# FPGA_Decoupling.net
KiCad netlist of a schematic drawn in Altium Designer
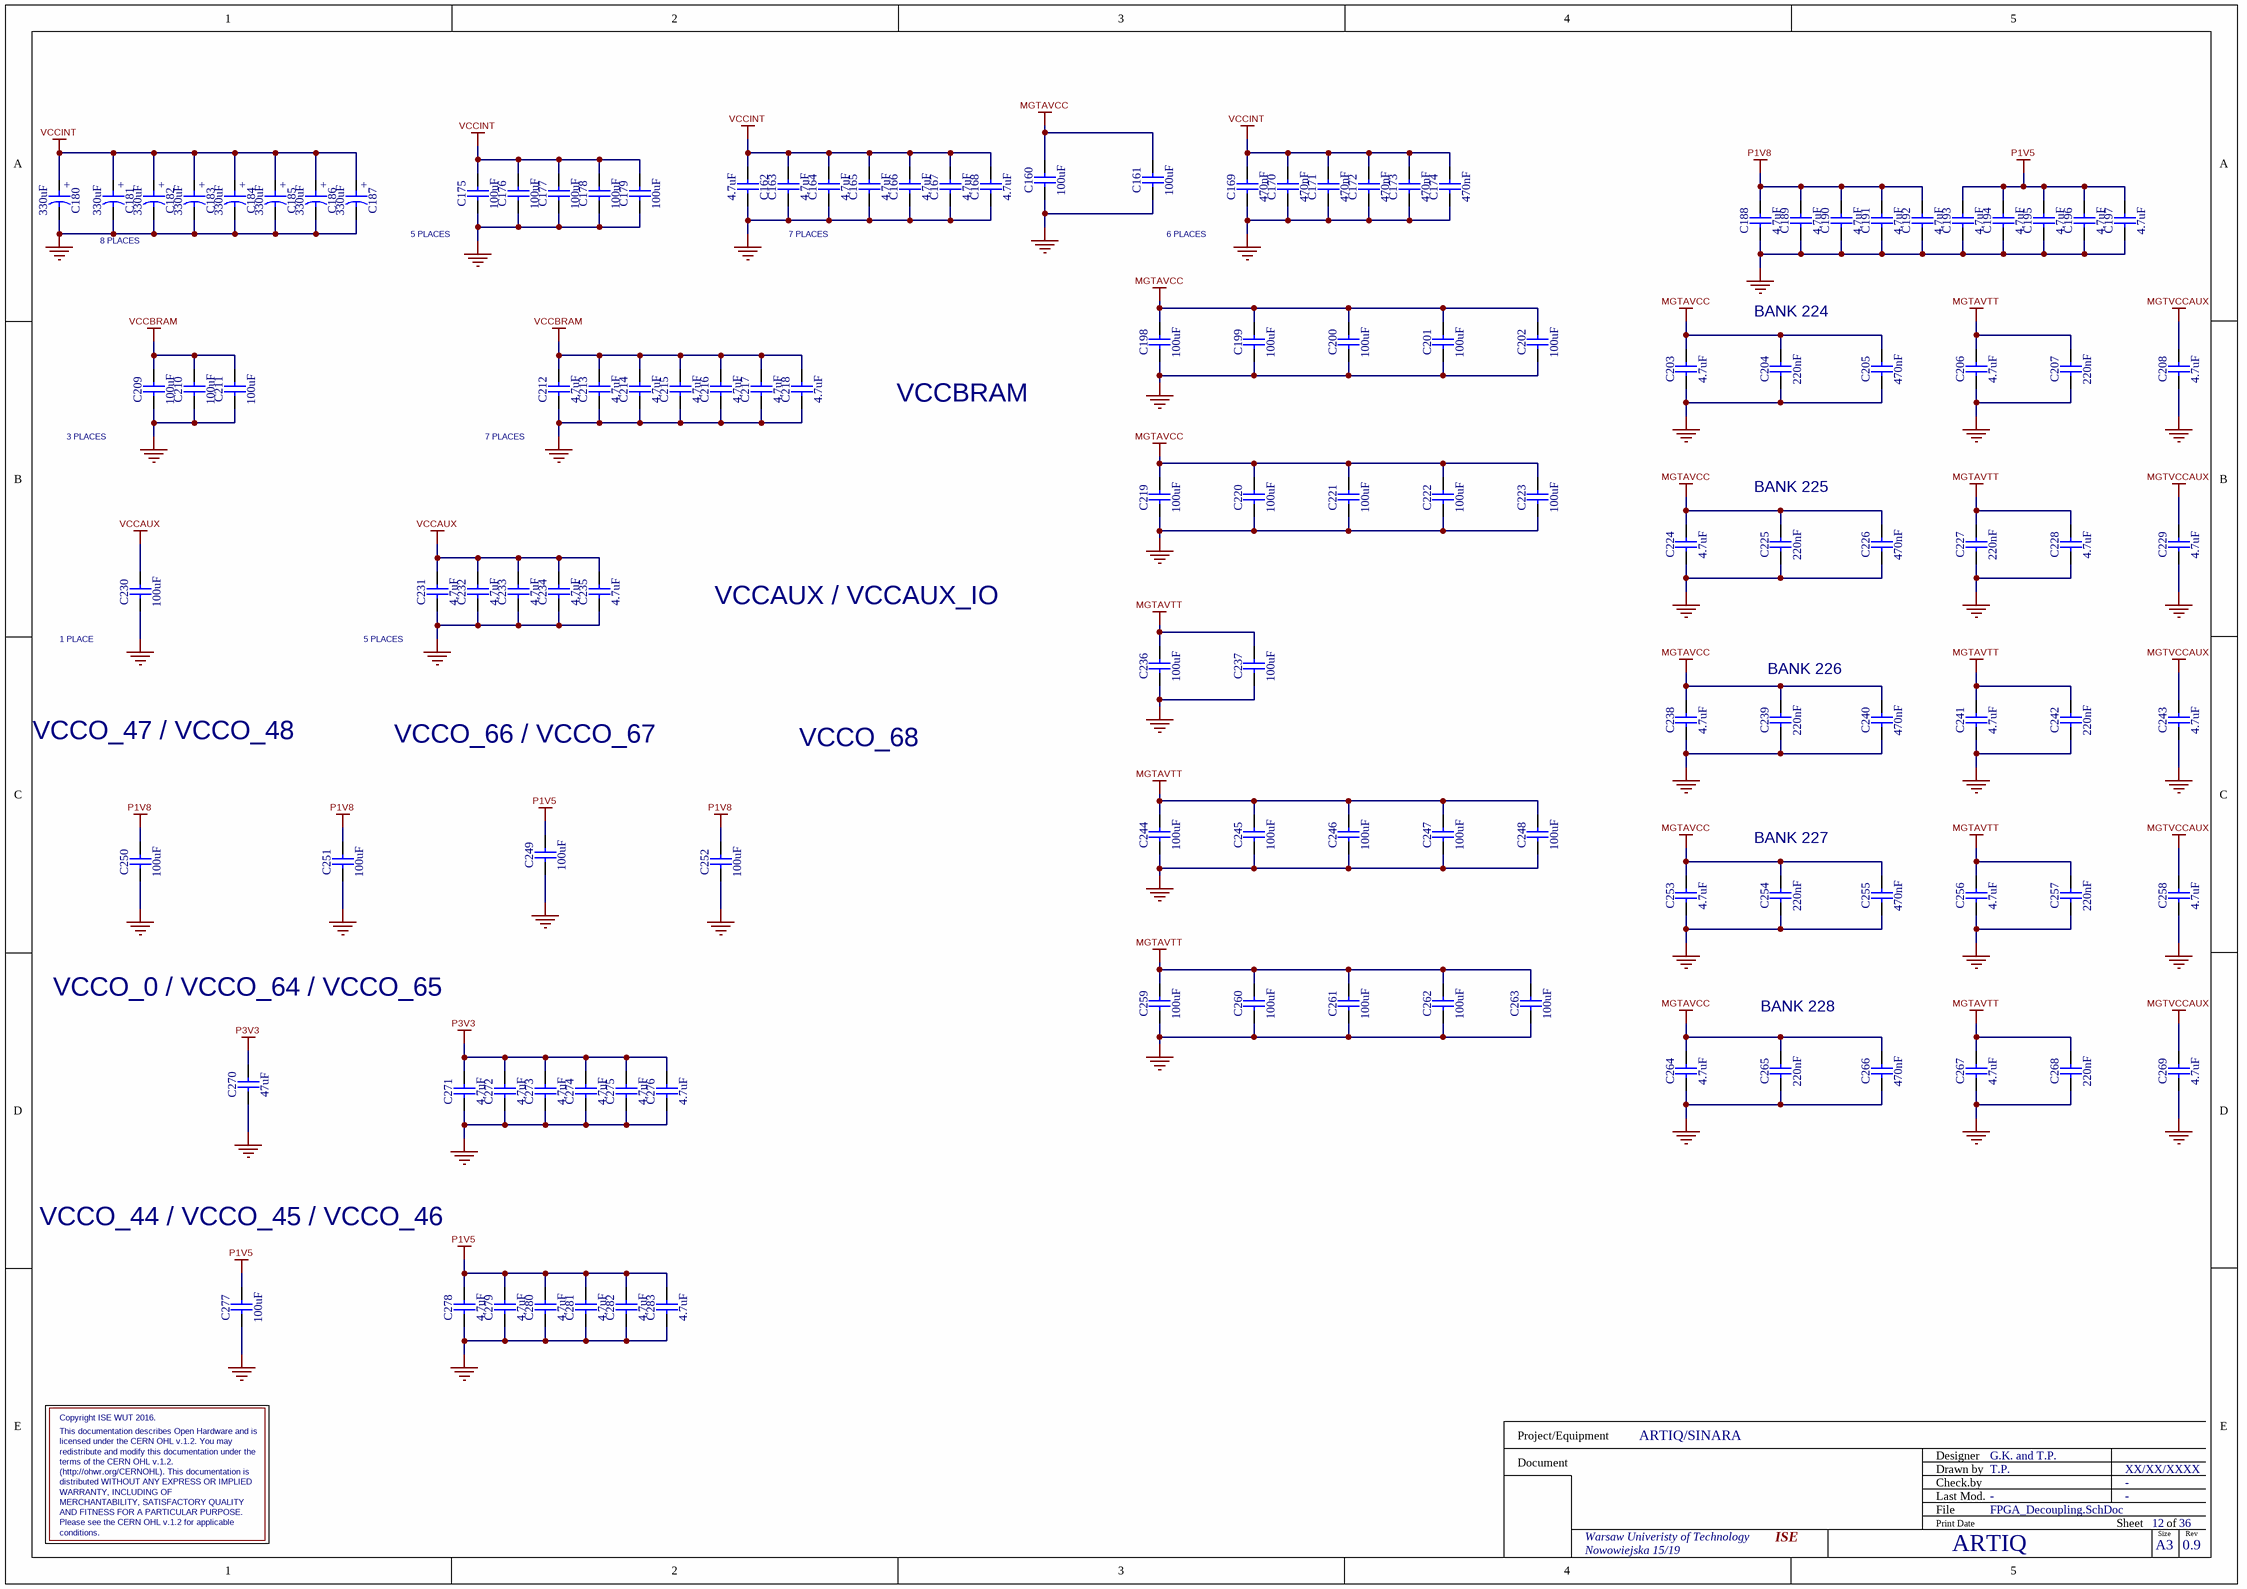
[diagram p0: FPGA_Decoupling.SchDoc]

(export (version "E")
  (design (tool "Eeschema 10.0.6"))
  (components
    (comp (ref "C160")
      (value "100uF")
      (footprint "CAPC3216X180N")
      (description "Non-polarised capacitor")
      (fields
        (field (name "MANUFACTURER PART NUMBER") "CC1206_100UF_6.3V_20%_X5R")
        (field (name "MANUFACTURER") "GENERIC")
        (field (name "AUTHOR") "CERN DEM JLC")
      )
      (libsource (lib "Capacitors") (part "Capacitor - non polarized"))
    )
    (comp (ref "C161")
      (value "100uF")
      (footprint "CAPC3216X180N")
      (description "Non-polarised capacitor")
      (fields
        (field (name "MANUFACTURER PART NUMBER") "CC1206_100UF_6.3V_20%_X5R")
        (field (name "MANUFACTURER") "GENERIC")
        (field (name "AUTHOR") "CERN DEM JLC")
      )
      (libsource (lib "Capacitors") (part "Capacitor - non polarized"))
    )
    (comp (ref "C162")
      (value "4.7uF")
      (footprint "CAPC1005X55N")
      (description "Non-polarised capacitor")
      (fields
        (field (name "MANUFACTURER PART NUMBER") "CC0402_4.7UF_6.3V_20%_X5R")
        (field (name "MANUFACTURER") "GENERIC")
        (field (name "AUTHOR") "CERN DEM JLC")
      )
      (libsource (lib "Capacitors") (part "Capacitor - non polarized"))
    )
    (comp (ref "C163")
      (value "4.7uF")
      (footprint "CAPC1005X55N")
      (description "Non-polarised capacitor")
      (fields
        (field (name "MANUFACTURER PART NUMBER") "CC0402_4.7UF_6.3V_20%_X5R")
        (field (name "MANUFACTURER") "GENERIC")
        (field (name "AUTHOR") "CERN DEM JLC")
      )
      (libsource (lib "Capacitors") (part "Capacitor - non polarized"))
    )
    (comp (ref "C164")
      (value "4.7uF")
      (footprint "CAPC1005X55N")
      (description "Non-polarised capacitor")
      (fields
        (field (name "MANUFACTURER PART NUMBER") "CC0402_4.7UF_6.3V_20%_X5R")
        (field (name "MANUFACTURER") "GENERIC")
        (field (name "AUTHOR") "CERN DEM JLC")
      )
      (libsource (lib "Capacitors") (part "Capacitor - non polarized"))
    )
    (comp (ref "C165")
      (value "4.7uF")
      (footprint "CAPC1005X55N")
      (description "Non-polarised capacitor")
      (fields
        (field (name "MANUFACTURER PART NUMBER") "CC0402_4.7UF_6.3V_20%_X5R")
        (field (name "MANUFACTURER") "GENERIC")
        (field (name "AUTHOR") "CERN DEM JLC")
      )
      (libsource (lib "Capacitors") (part "Capacitor - non polarized"))
    )
    (comp (ref "C166")
      (value "4.7uF")
      (footprint "CAPC1005X55N")
      (description "Non-polarised capacitor")
      (fields
        (field (name "MANUFACTURER PART NUMBER") "CC0402_4.7UF_6.3V_20%_X5R")
        (field (name "MANUFACTURER") "GENERIC")
        (field (name "AUTHOR") "CERN DEM JLC")
      )
      (libsource (lib "Capacitors") (part "Capacitor - non polarized"))
    )
    (comp (ref "C167")
      (value "4.7uF")
      (footprint "CAPC1005X55N")
      (description "Non-polarised capacitor")
      (fields
        (field (name "MANUFACTURER PART NUMBER") "CC0402_4.7UF_6.3V_20%_X5R")
        (field (name "MANUFACTURER") "GENERIC")
        (field (name "AUTHOR") "CERN DEM JLC")
      )
      (libsource (lib "Capacitors") (part "Capacitor - non polarized"))
    )
    (comp (ref "C168")
      (value "4.7uF")
      (footprint "CAPC1005X55N")
      (description "Non-polarised capacitor")
      (fields
        (field (name "MANUFACTURER PART NUMBER") "CC0402_4.7UF_6.3V_20%_X5R")
        (field (name "MANUFACTURER") "GENERIC")
        (field (name "AUTHOR") "CERN DEM JLC")
      )
      (libsource (lib "Capacitors") (part "Capacitor - non polarized"))
    )
    (comp (ref "C169")
      (value "470nF")
      (footprint "CAPC0603X33N")
      (description "Non-polarised capacitor")
      (fields
        (field (name "MANUFACTURER PART NUMBER") "CC0201_470NF_4V_20%_X5R")
        (field (name "MANUFACTURER") "GENERIC")
        (field (name "AUTHOR") "CERN DEM JLC")
      )
      (libsource (lib "Capacitors") (part "Capacitor - non polarized"))
    )
    (comp (ref "C170")
      (value "470nF")
      (footprint "CAPC0603X33N")
      (description "Non-polarised capacitor")
      (fields
        (field (name "MANUFACTURER PART NUMBER") "CC0201_470NF_4V_20%_X5R")
        (field (name "MANUFACTURER") "GENERIC")
        (field (name "AUTHOR") "CERN DEM JLC")
      )
      (libsource (lib "Capacitors") (part "Capacitor - non polarized"))
    )
    (comp (ref "C171")
      (value "470nF")
      (footprint "CAPC0603X33N")
      (description "Non-polarised capacitor")
      (fields
        (field (name "MANUFACTURER PART NUMBER") "CC0201_470NF_4V_20%_X5R")
        (field (name "MANUFACTURER") "GENERIC")
        (field (name "AUTHOR") "CERN DEM JLC")
      )
      (libsource (lib "Capacitors") (part "Capacitor - non polarized"))
    )
    (comp (ref "C172")
      (value "470nF")
      (footprint "CAPC0603X33N")
      (description "Non-polarised capacitor")
      (fields
        (field (name "MANUFACTURER PART NUMBER") "CC0201_470NF_4V_20%_X5R")
        (field (name "MANUFACTURER") "GENERIC")
        (field (name "AUTHOR") "CERN DEM JLC")
      )
      (libsource (lib "Capacitors") (part "Capacitor - non polarized"))
    )
    (comp (ref "C173")
      (value "470nF")
      (footprint "CAPC0603X33N")
      (description "Non-polarised capacitor")
      (fields
        (field (name "MANUFACTURER PART NUMBER") "CC0201_470NF_4V_20%_X5R")
        (field (name "MANUFACTURER") "GENERIC")
        (field (name "AUTHOR") "CERN DEM JLC")
      )
      (libsource (lib "Capacitors") (part "Capacitor - non polarized"))
    )
    (comp (ref "C174")
      (value "470nF")
      (footprint "CAPC0603X33N")
      (description "Non-polarised capacitor")
      (fields
        (field (name "MANUFACTURER PART NUMBER") "CC0201_470NF_4V_20%_X5R")
        (field (name "MANUFACTURER") "GENERIC")
        (field (name "AUTHOR") "CERN DEM JLC")
      )
      (libsource (lib "Capacitors") (part "Capacitor - non polarized"))
    )
    (comp (ref "C175")
      (value "100uF")
      (footprint "CAPC3216X180N")
      (description "Non-polarised capacitor")
      (fields
        (field (name "MANUFACTURER PART NUMBER") "CC1206_100UF_6.3V_20%_X5R")
        (field (name "MANUFACTURER") "GENERIC")
        (field (name "AUTHOR") "CERN DEM JLC")
      )
      (libsource (lib "Capacitors") (part "Capacitor - non polarized"))
    )
    (comp (ref "C176")
      (value "100uF")
      (footprint "CAPC3216X180N")
      (description "Non-polarised capacitor")
      (fields
        (field (name "MANUFACTURER PART NUMBER") "CC1206_100UF_6.3V_20%_X5R")
        (field (name "MANUFACTURER") "GENERIC")
        (field (name "AUTHOR") "CERN DEM JLC")
      )
      (libsource (lib "Capacitors") (part "Capacitor - non polarized"))
    )
    (comp (ref "C177")
      (value "100uF")
      (footprint "CAPC3216X180N")
      (description "Non-polarised capacitor")
      (fields
        (field (name "MANUFACTURER PART NUMBER") "CC1206_100UF_6.3V_20%_X5R")
        (field (name "MANUFACTURER") "GENERIC")
        (field (name "AUTHOR") "CERN DEM JLC")
      )
      (libsource (lib "Capacitors") (part "Capacitor - non polarized"))
    )
    (comp (ref "C178")
      (value "100uF")
      (footprint "CAPC3216X180N")
      (description "Non-polarised capacitor")
      (fields
        (field (name "MANUFACTURER PART NUMBER") "CC1206_100UF_6.3V_20%_X5R")
        (field (name "MANUFACTURER") "GENERIC")
        (field (name "AUTHOR") "CERN DEM JLC")
      )
      (libsource (lib "Capacitors") (part "Capacitor - non polarized"))
    )
    (comp (ref "C179")
      (value "100uF")
      (footprint "CAPC3216X180N")
      (description "Non-polarised capacitor")
      (fields
        (field (name "MANUFACTURER PART NUMBER") "CC1206_100UF_6.3V_20%_X5R")
        (field (name "MANUFACTURER") "GENERIC")
        (field (name "AUTHOR") "CERN DEM JLC")
      )
      (libsource (lib "Capacitors") (part "Capacitor - non polarized"))
    )
    (comp (ref "C180")
      (value "330uF")
      (footprint "CAPMP3528X210N")
      (description "Polarised capacitor")
      (fields
        (field (name "MANUFACTURER PART NUMBER") "T520B337M2R5ATE015")
        (field (name "MANUFACTURER") "KEMET")
        (field (name "AUTHOR") "CERN DEM JLC")
      )
      (libsource (lib "Capacitors") (part "Capacitor - polarized"))
    )
    (comp (ref "C181")
      (value "330uF")
      (footprint "CAPMP3528X210N")
      (description "Polarised capacitor")
      (fields
        (field (name "MANUFACTURER PART NUMBER") "T520B337M2R5ATE015")
        (field (name "MANUFACTURER") "KEMET")
        (field (name "AUTHOR") "CERN DEM JLC")
      )
      (libsource (lib "Capacitors") (part "Capacitor - polarized"))
    )
    (comp (ref "C182")
      (value "330uF")
      (footprint "CAPMP3528X210N")
      (description "Polarised capacitor")
      (fields
        (field (name "MANUFACTURER PART NUMBER") "T520B337M2R5ATE015")
        (field (name "MANUFACTURER") "KEMET")
        (field (name "AUTHOR") "CERN DEM JLC")
      )
      (libsource (lib "Capacitors") (part "Capacitor - polarized"))
    )
    (comp (ref "C183")
      (value "330uF")
      (footprint "CAPMP3528X210N")
      (description "Polarised capacitor")
      (fields
        (field (name "MANUFACTURER PART NUMBER") "T520B337M2R5ATE015")
        (field (name "MANUFACTURER") "KEMET")
        (field (name "AUTHOR") "CERN DEM JLC")
      )
      (libsource (lib "Capacitors") (part "Capacitor - polarized"))
    )
    (comp (ref "C184")
      (value "330uF")
      (footprint "CAPMP3528X210N")
      (description "Polarised capacitor")
      (fields
        (field (name "MANUFACTURER PART NUMBER") "T520B337M2R5ATE015")
        (field (name "MANUFACTURER") "KEMET")
        (field (name "AUTHOR") "CERN DEM JLC")
      )
      (libsource (lib "Capacitors") (part "Capacitor - polarized"))
    )
    (comp (ref "C185")
      (value "330uF")
      (footprint "CAPMP3528X210N")
      (description "Polarised capacitor")
      (fields
        (field (name "MANUFACTURER PART NUMBER") "T520B337M2R5ATE015")
        (field (name "MANUFACTURER") "KEMET")
        (field (name "AUTHOR") "CERN DEM JLC")
      )
      (libsource (lib "Capacitors") (part "Capacitor - polarized"))
    )
    (comp (ref "C186")
      (value "330uF")
      (footprint "CAPMP3528X210N")
      (description "Polarised capacitor")
      (fields
        (field (name "MANUFACTURER PART NUMBER") "T520B337M2R5ATE015")
        (field (name "MANUFACTURER") "KEMET")
        (field (name "AUTHOR") "CERN DEM JLC")
      )
      (libsource (lib "Capacitors") (part "Capacitor - polarized"))
    )
    (comp (ref "C187")
      (value "330uF")
      (footprint "CAPMP3528X210N")
      (description "Polarised capacitor")
      (fields
        (field (name "MANUFACTURER PART NUMBER") "T520B337M2R5ATE015")
        (field (name "MANUFACTURER") "KEMET")
        (field (name "AUTHOR") "CERN DEM JLC")
      )
      (libsource (lib "Capacitors") (part "Capacitor - polarized"))
    )
    (comp (ref "C188")
      (value "4.7uF")
      (footprint "CAPC1005X55N")
      (description "Non-polarised capacitor")
      (fields
        (field (name "MANUFACTURER PART NUMBER") "CC0402_4.7UF_6.3V_20%_X5R")
        (field (name "MANUFACTURER") "GENERIC")
        (field (name "AUTHOR") "CERN DEM JLC")
      )
      (libsource (lib "Capacitors") (part "Capacitor - non polarized"))
    )
    (comp (ref "C189")
      (value "4.7uF")
      (footprint "CAPC1005X55N")
      (description "Non-polarised capacitor")
      (fields
        (field (name "MANUFACTURER PART NUMBER") "CC0402_4.7UF_6.3V_20%_X5R")
        (field (name "MANUFACTURER") "GENERIC")
        (field (name "AUTHOR") "CERN DEM JLC")
      )
      (libsource (lib "Capacitors") (part "Capacitor - non polarized"))
    )
    (comp (ref "C190")
      (value "4.7uF")
      (footprint "CAPC1005X55N")
      (description "Non-polarised capacitor")
      (fields
        (field (name "MANUFACTURER PART NUMBER") "CC0402_4.7UF_6.3V_20%_X5R")
        (field (name "MANUFACTURER") "GENERIC")
        (field (name "AUTHOR") "CERN DEM JLC")
      )
      (libsource (lib "Capacitors") (part "Capacitor - non polarized"))
    )
    (comp (ref "C191")
      (value "4.7uF")
      (footprint "CAPC1005X55N")
      (description "Non-polarised capacitor")
      (fields
        (field (name "MANUFACTURER PART NUMBER") "CC0402_4.7UF_6.3V_20%_X5R")
        (field (name "MANUFACTURER") "GENERIC")
        (field (name "AUTHOR") "CERN DEM JLC")
      )
      (libsource (lib "Capacitors") (part "Capacitor - non polarized"))
    )
    (comp (ref "C192")
      (value "4.7uF")
      (footprint "CAPC1005X55N")
      (description "Non-polarised capacitor")
      (fields
        (field (name "MANUFACTURER PART NUMBER") "CC0402_4.7UF_6.3V_20%_X5R")
        (field (name "MANUFACTURER") "GENERIC")
        (field (name "AUTHOR") "CERN DEM JLC")
      )
      (libsource (lib "Capacitors") (part "Capacitor - non polarized"))
    )
    (comp (ref "C193")
      (value "4.7uF")
      (footprint "CAPC1005X55N")
      (description "Non-polarised capacitor")
      (fields
        (field (name "MANUFACTURER PART NUMBER") "CC0402_4.7UF_6.3V_20%_X5R")
        (field (name "MANUFACTURER") "GENERIC")
        (field (name "AUTHOR") "CERN DEM JLC")
      )
      (libsource (lib "Capacitors") (part "Capacitor - non polarized"))
    )
    (comp (ref "C194")
      (value "4.7uF")
      (footprint "CAPC1005X55N")
      (description "Non-polarised capacitor")
      (fields
        (field (name "MANUFACTURER PART NUMBER") "CC0402_4.7UF_6.3V_20%_X5R")
        (field (name "MANUFACTURER") "GENERIC")
        (field (name "AUTHOR") "CERN DEM JLC")
      )
      (libsource (lib "Capacitors") (part "Capacitor - non polarized"))
    )
    (comp (ref "C195")
      (value "4.7uF")
      (footprint "CAPC1005X55N")
      (description "Non-polarised capacitor")
      (fields
        (field (name "MANUFACTURER PART NUMBER") "CC0402_4.7UF_6.3V_20%_X5R")
        (field (name "MANUFACTURER") "GENERIC")
        (field (name "AUTHOR") "CERN DEM JLC")
      )
      (libsource (lib "Capacitors") (part "Capacitor - non polarized"))
    )
    (comp (ref "C196")
      (value "4.7uF")
      (footprint "CAPC1005X55N")
      (description "Non-polarised capacitor")
      (fields
        (field (name "MANUFACTURER PART NUMBER") "CC0402_4.7UF_6.3V_20%_X5R")
        (field (name "MANUFACTURER") "GENERIC")
        (field (name "AUTHOR") "CERN DEM JLC")
      )
      (libsource (lib "Capacitors") (part "Capacitor - non polarized"))
    )
    (comp (ref "C197")
      (value "4.7uF")
      (footprint "CAPC1005X55N")
      (description "Non-polarised capacitor")
      (fields
        (field (name "MANUFACTURER PART NUMBER") "CC0402_4.7UF_6.3V_20%_X5R")
        (field (name "MANUFACTURER") "GENERIC")
        (field (name "AUTHOR") "CERN DEM JLC")
      )
      (libsource (lib "Capacitors") (part "Capacitor - non polarized"))
    )
    (comp (ref "C198")
      (value "100uF")
      (footprint "CAPC3216X180N")
      (description "Non-polarised capacitor")
      (fields
        (field (name "MANUFACTURER PART NUMBER") "CC1206_100UF_6.3V_20%_X5R")
        (field (name "MANUFACTURER") "GENERIC")
        (field (name "AUTHOR") "CERN DEM JLC")
      )
      (libsource (lib "Capacitors") (part "Capacitor - non polarized"))
    )
    (comp (ref "C199")
      (value "100uF")
      (footprint "CAPC3216X180N")
      (description "Non-polarised capacitor")
      (fields
        (field (name "MANUFACTURER PART NUMBER") "CC1206_100UF_6.3V_20%_X5R")
        (field (name "MANUFACTURER") "GENERIC")
        (field (name "AUTHOR") "CERN DEM JLC")
      )
      (libsource (lib "Capacitors") (part "Capacitor - non polarized"))
    )
    (comp (ref "C200")
      (value "100uF")
      (footprint "CAPC3216X180N")
      (description "Non-polarised capacitor")
      (fields
        (field (name "MANUFACTURER PART NUMBER") "CC1206_100UF_6.3V_20%_X5R")
        (field (name "MANUFACTURER") "GENERIC")
        (field (name "AUTHOR") "CERN DEM JLC")
      )
      (libsource (lib "Capacitors") (part "Capacitor - non polarized"))
    )
    (comp (ref "C201")
      (value "100uF")
      (footprint "CAPC3216X180N")
      (description "Non-polarised capacitor")
      (fields
        (field (name "MANUFACTURER PART NUMBER") "CC1206_100UF_6.3V_20%_X5R")
        (field (name "MANUFACTURER") "GENERIC")
        (field (name "AUTHOR") "CERN DEM JLC")
      )
      (libsource (lib "Capacitors") (part "Capacitor - non polarized"))
    )
    (comp (ref "C202")
      (value "100uF")
      (footprint "CAPC3216X180N")
      (description "Non-polarised capacitor")
      (fields
        (field (name "MANUFACTURER PART NUMBER") "CC1206_100UF_6.3V_20%_X5R")
        (field (name "MANUFACTURER") "GENERIC")
        (field (name "AUTHOR") "CERN DEM JLC")
      )
      (libsource (lib "Capacitors") (part "Capacitor - non polarized"))
    )
    (comp (ref "C203")
      (value "4.7uF")
      (footprint "CAPC1005X55N")
      (description "Non-polarised capacitor")
      (fields
        (field (name "MANUFACTURER PART NUMBER") "CC0402_4.7UF_6.3V_20%_X5R")
        (field (name "MANUFACTURER") "GENERIC")
        (field (name "AUTHOR") "CERN DEM JLC")
      )
      (libsource (lib "Capacitors") (part "Capacitor - non polarized"))
    )
    (comp (ref "C204")
      (value "220nF")
      (footprint "CAPC0603X33N")
      (description "Non-polarised capacitor")
      (fields
        (field (name "MANUFACTURER PART NUMBER") "CC0201_220NF_6.3V_20%_X5R")
        (field (name "MANUFACTURER") "GENERIC")
        (field (name "AUTHOR") "CERN DEM JLC")
      )
      (libsource (lib "Capacitors") (part "Capacitor - non polarized"))
    )
    (comp (ref "C205")
      (value "470nF")
      (footprint "CAPC0603X33N")
      (description "Non-polarised capacitor")
      (fields
        (field (name "MANUFACTURER PART NUMBER") "CC0201_470NF_4V_20%_X5R")
        (field (name "MANUFACTURER") "GENERIC")
        (field (name "AUTHOR") "CERN DEM JLC")
      )
      (libsource (lib "Capacitors") (part "Capacitor - non polarized"))
    )
    (comp (ref "C206")
      (value "4.7uF")
      (footprint "CAPC1005X55N")
      (description "Non-polarised capacitor")
      (fields
        (field (name "MANUFACTURER PART NUMBER") "CC0402_4.7UF_6.3V_20%_X5R")
        (field (name "MANUFACTURER") "GENERIC")
        (field (name "AUTHOR") "CERN DEM JLC")
      )
      (libsource (lib "Capacitors") (part "Capacitor - non polarized"))
    )
    (comp (ref "C207")
      (value "220nF")
      (footprint "CAPC0603X33N")
      (description "Non-polarised capacitor")
      (fields
        (field (name "MANUFACTURER PART NUMBER") "CC0201_220NF_6.3V_20%_X5R")
        (field (name "MANUFACTURER") "GENERIC")
        (field (name "AUTHOR") "CERN DEM JLC")
      )
      (libsource (lib "Capacitors") (part "Capacitor - non polarized"))
    )
    (comp (ref "C208")
      (value "4.7uF")
      (footprint "CAPC1005X55N")
      (description "Non-polarised capacitor")
      (fields
        (field (name "MANUFACTURER PART NUMBER") "CC0402_4.7UF_6.3V_20%_X5R")
        (field (name "MANUFACTURER") "GENERIC")
        (field (name "AUTHOR") "CERN DEM JLC")
      )
      (libsource (lib "Capacitors") (part "Capacitor - non polarized"))
    )
    (comp (ref "C209")
      (value "100uF")
      (footprint "CAPC3216X180N")
      (description "Non-polarised capacitor")
      (fields
        (field (name "MANUFACTURER PART NUMBER") "CC1206_100UF_6.3V_20%_X5R")
        (field (name "MANUFACTURER") "GENERIC")
        (field (name "AUTHOR") "CERN DEM JLC")
      )
      (libsource (lib "Capacitors") (part "Capacitor - non polarized"))
    )
    (comp (ref "C210")
      (value "100uF")
      (footprint "CAPC3216X180N")
      (description "Non-polarised capacitor")
      (fields
        (field (name "MANUFACTURER PART NUMBER") "CC1206_100UF_6.3V_20%_X5R")
        (field (name "MANUFACTURER") "GENERIC")
        (field (name "AUTHOR") "CERN DEM JLC")
      )
      (libsource (lib "Capacitors") (part "Capacitor - non polarized"))
    )
    (comp (ref "C211")
      (value "100uF")
      (footprint "CAPC3216X180N")
      (description "Non-polarised capacitor")
      (fields
        (field (name "MANUFACTURER PART NUMBER") "CC1206_100UF_6.3V_20%_X5R")
        (field (name "MANUFACTURER") "GENERIC")
        (field (name "AUTHOR") "CERN DEM JLC")
      )
      (libsource (lib "Capacitors") (part "Capacitor - non polarized"))
    )
    (comp (ref "C212")
      (value "4.7uF")
      (footprint "CAPC1005X55N")
      (description "Non-polarised capacitor")
      (fields
        (field (name "MANUFACTURER PART NUMBER") "CC0402_4.7UF_6.3V_20%_X5R")
        (field (name "MANUFACTURER") "GENERIC")
        (field (name "AUTHOR") "CERN DEM JLC")
      )
      (libsource (lib "Capacitors") (part "Capacitor - non polarized"))
    )
    (comp (ref "C213")
      (value "4.7uF")
      (footprint "CAPC1005X55N")
      (description "Non-polarised capacitor")
      (fields
        (field (name "MANUFACTURER PART NUMBER") "CC0402_4.7UF_6.3V_20%_X5R")
        (field (name "MANUFACTURER") "GENERIC")
        (field (name "AUTHOR") "CERN DEM JLC")
      )
      (libsource (lib "Capacitors") (part "Capacitor - non polarized"))
    )
    (comp (ref "C214")
      (value "4.7uF")
      (footprint "CAPC1005X55N")
      (description "Non-polarised capacitor")
      (fields
        (field (name "MANUFACTURER PART NUMBER") "CC0402_4.7UF_6.3V_20%_X5R")
        (field (name "MANUFACTURER") "GENERIC")
        (field (name "AUTHOR") "CERN DEM JLC")
      )
      (libsource (lib "Capacitors") (part "Capacitor - non polarized"))
    )
    (comp (ref "C215")
      (value "4.7uF")
      (footprint "CAPC1005X55N")
      (description "Non-polarised capacitor")
      (fields
        (field (name "MANUFACTURER PART NUMBER") "CC0402_4.7UF_6.3V_20%_X5R")
        (field (name "MANUFACTURER") "GENERIC")
        (field (name "AUTHOR") "CERN DEM JLC")
      )
      (libsource (lib "Capacitors") (part "Capacitor - non polarized"))
    )
    (comp (ref "C216")
      (value "4.7uF")
      (footprint "CAPC1005X55N")
      (description "Non-polarised capacitor")
      (fields
        (field (name "MANUFACTURER PART NUMBER") "CC0402_4.7UF_6.3V_20%_X5R")
        (field (name "MANUFACTURER") "GENERIC")
        (field (name "AUTHOR") "CERN DEM JLC")
      )
      (libsource (lib "Capacitors") (part "Capacitor - non polarized"))
    )
    (comp (ref "C217")
      (value "4.7uF")
      (footprint "CAPC1005X55N")
      (description "Non-polarised capacitor")
      (fields
        (field (name "MANUFACTURER PART NUMBER") "CC0402_4.7UF_6.3V_20%_X5R")
        (field (name "MANUFACTURER") "GENERIC")
        (field (name "AUTHOR") "CERN DEM JLC")
      )
      (libsource (lib "Capacitors") (part "Capacitor - non polarized"))
    )
    (comp (ref "C218")
      (value "4.7uF")
      (footprint "CAPC1005X55N")
      (description "Non-polarised capacitor")
      (fields
        (field (name "MANUFACTURER PART NUMBER") "CC0402_4.7UF_6.3V_20%_X5R")
        (field (name "MANUFACTURER") "GENERIC")
        (field (name "AUTHOR") "CERN DEM JLC")
      )
      (libsource (lib "Capacitors") (part "Capacitor - non polarized"))
    )
    (comp (ref "C219")
      (value "100uF")
      (footprint "CAPC3216X180N")
      (description "Non-polarised capacitor")
      (fields
        (field (name "MANUFACTURER PART NUMBER") "CC1206_100UF_6.3V_20%_X5R")
        (field (name "MANUFACTURER") "GENERIC")
        (field (name "AUTHOR") "CERN DEM JLC")
      )
      (libsource (lib "Capacitors") (part "Capacitor - non polarized"))
    )
    (comp (ref "C220")
      (value "100uF")
      (footprint "CAPC3216X180N")
      (description "Non-polarised capacitor")
      (fields
        (field (name "MANUFACTURER PART NUMBER") "CC1206_100UF_6.3V_20%_X5R")
        (field (name "MANUFACTURER") "GENERIC")
        (field (name "AUTHOR") "CERN DEM JLC")
      )
      (libsource (lib "Capacitors") (part "Capacitor - non polarized"))
    )
    (comp (ref "C221")
      (value "100uF")
      (footprint "CAPC3216X180N")
      (description "Non-polarised capacitor")
      (fields
        (field (name "MANUFACTURER PART NUMBER") "CC1206_100UF_6.3V_20%_X5R")
        (field (name "MANUFACTURER") "GENERIC")
        (field (name "AUTHOR") "CERN DEM JLC")
      )
      (libsource (lib "Capacitors") (part "Capacitor - non polarized"))
    )
    (comp (ref "C222")
      (value "100uF")
      (footprint "CAPC3216X180N")
      (description "Non-polarised capacitor")
      (fields
        (field (name "MANUFACTURER PART NUMBER") "CC1206_100UF_6.3V_20%_X5R")
        (field (name "MANUFACTURER") "GENERIC")
        (field (name "AUTHOR") "CERN DEM JLC")
      )
      (libsource (lib "Capacitors") (part "Capacitor - non polarized"))
    )
    (comp (ref "C223")
      (value "100uF")
      (footprint "CAPC3216X180N")
      (description "Non-polarised capacitor")
      (fields
        (field (name "MANUFACTURER PART NUMBER") "CC1206_100UF_6.3V_20%_X5R")
        (field (name "MANUFACTURER") "GENERIC")
        (field (name "AUTHOR") "CERN DEM JLC")
      )
      (libsource (lib "Capacitors") (part "Capacitor - non polarized"))
    )
    (comp (ref "C224")
      (value "4.7uF")
      (footprint "CAPC1005X55N")
      (description "Non-polarised capacitor")
      (fields
        (field (name "MANUFACTURER PART NUMBER") "CC0402_4.7UF_6.3V_20%_X5R")
        (field (name "MANUFACTURER") "GENERIC")
        (field (name "AUTHOR") "CERN DEM JLC")
      )
      (libsource (lib "Capacitors") (part "Capacitor - non polarized"))
    )
    (comp (ref "C225")
      (value "220nF")
      (footprint "CAPC0603X33N")
      (description "Non-polarised capacitor")
      (fields
        (field (name "MANUFACTURER PART NUMBER") "CC0201_220NF_6.3V_20%_X5R")
        (field (name "MANUFACTURER") "GENERIC")
        (field (name "AUTHOR") "CERN DEM JLC")
      )
      (libsource (lib "Capacitors") (part "Capacitor - non polarized"))
    )
    (comp (ref "C226")
      (value "470nF")
      (footprint "CAPC0603X33N")
      (description "Non-polarised capacitor")
      (fields
        (field (name "MANUFACTURER PART NUMBER") "CC0201_470NF_4V_20%_X5R")
        (field (name "MANUFACTURER") "GENERIC")
        (field (name "AUTHOR") "CERN DEM JLC")
      )
      (libsource (lib "Capacitors") (part "Capacitor - non polarized"))
    )
    (comp (ref "C227")
      (value "220nF")
      (footprint "CAPC0603X33N")
      (description "Non-polarised capacitor")
      (fields
        (field (name "MANUFACTURER PART NUMBER") "CC0201_220NF_6.3V_20%_X5R")
        (field (name "MANUFACTURER") "GENERIC")
        (field (name "AUTHOR") "CERN DEM JLC")
      )
      (libsource (lib "Capacitors") (part "Capacitor - non polarized"))
    )
    (comp (ref "C228")
      (value "4.7uF")
      (footprint "CAPC1005X55N")
      (description "Non-polarised capacitor")
      (fields
        (field (name "MANUFACTURER PART NUMBER") "CC0402_4.7UF_6.3V_20%_X5R")
        (field (name "MANUFACTURER") "GENERIC")
        (field (name "AUTHOR") "CERN DEM JLC")
      )
      (libsource (lib "Capacitors") (part "Capacitor - non polarized"))
    )
    (comp (ref "C229")
      (value "4.7uF")
      (footprint "CAPC1005X55N")
      (description "Non-polarised capacitor")
      (fields
        (field (name "MANUFACTURER PART NUMBER") "CC0402_4.7UF_6.3V_20%_X5R")
        (field (name "MANUFACTURER") "GENERIC")
        (field (name "AUTHOR") "CERN DEM JLC")
      )
      (libsource (lib "Capacitors") (part "Capacitor - non polarized"))
    )
    (comp (ref "C230")
      (value "100uF")
      (footprint "CAPC3216X180N")
      (description "Non-polarised capacitor")
      (fields
        (field (name "MANUFACTURER PART NUMBER") "CC1206_100UF_6.3V_20%_X5R")
        (field (name "MANUFACTURER") "GENERIC")
        (field (name "AUTHOR") "CERN DEM JLC")
      )
      (libsource (lib "Capacitors") (part "Capacitor - non polarized"))
    )
    (comp (ref "C231")
      (value "4.7uF")
      (footprint "CAPC1005X55N")
      (description "Non-polarised capacitor")
      (fields
        (field (name "MANUFACTURER PART NUMBER") "CC0402_4.7UF_6.3V_20%_X5R")
        (field (name "MANUFACTURER") "GENERIC")
        (field (name "AUTHOR") "CERN DEM JLC")
      )
      (libsource (lib "Capacitors") (part "Capacitor - non polarized"))
    )
    (comp (ref "C232")
      (value "4.7uF")
      (footprint "CAPC1005X55N")
      (description "Non-polarised capacitor")
      (fields
        (field (name "MANUFACTURER PART NUMBER") "CC0402_4.7UF_6.3V_20%_X5R")
        (field (name "MANUFACTURER") "GENERIC")
        (field (name "AUTHOR") "CERN DEM JLC")
      )
      (libsource (lib "Capacitors") (part "Capacitor - non polarized"))
    )
    (comp (ref "C233")
      (value "4.7uF")
      (footprint "CAPC1005X55N")
      (description "Non-polarised capacitor")
      (fields
        (field (name "MANUFACTURER PART NUMBER") "CC0402_4.7UF_6.3V_20%_X5R")
        (field (name "MANUFACTURER") "GENERIC")
        (field (name "AUTHOR") "CERN DEM JLC")
      )
      (libsource (lib "Capacitors") (part "Capacitor - non polarized"))
    )
    (comp (ref "C234")
      (value "4.7uF")
      (footprint "CAPC1005X55N")
      (description "Non-polarised capacitor")
      (fields
        (field (name "MANUFACTURER PART NUMBER") "CC0402_4.7UF_6.3V_20%_X5R")
        (field (name "MANUFACTURER") "GENERIC")
        (field (name "AUTHOR") "CERN DEM JLC")
      )
      (libsource (lib "Capacitors") (part "Capacitor - non polarized"))
    )
    (comp (ref "C235")
      (value "4.7uF")
      (footprint "CAPC1005X55N")
      (description "Non-polarised capacitor")
      (fields
        (field (name "MANUFACTURER PART NUMBER") "CC0402_4.7UF_6.3V_20%_X5R")
        (field (name "MANUFACTURER") "GENERIC")
        (field (name "AUTHOR") "CERN DEM JLC")
      )
      (libsource (lib "Capacitors") (part "Capacitor - non polarized"))
    )
    (comp (ref "C236")
      (value "100uF")
      (footprint "CAPC3216X180N")
      (description "Non-polarised capacitor")
      (fields
        (field (name "MANUFACTURER PART NUMBER") "CC1206_100UF_6.3V_20%_X5R")
        (field (name "MANUFACTURER") "GENERIC")
        (field (name "AUTHOR") "CERN DEM JLC")
      )
      (libsource (lib "Capacitors") (part "Capacitor - non polarized"))
    )
    (comp (ref "C237")
      (value "100uF")
      (footprint "CAPC3216X180N")
      (description "Non-polarised capacitor")
      (fields
        (field (name "MANUFACTURER PART NUMBER") "CC1206_100UF_6.3V_20%_X5R")
        (field (name "MANUFACTURER") "GENERIC")
        (field (name "AUTHOR") "CERN DEM JLC")
      )
      (libsource (lib "Capacitors") (part "Capacitor - non polarized"))
    )
    (comp (ref "C238")
      (value "4.7uF")
      (footprint "CAPC1005X55N")
      (description "Non-polarised capacitor")
      (fields
        (field (name "MANUFACTURER PART NUMBER") "CC0402_4.7UF_6.3V_20%_X5R")
        (field (name "MANUFACTURER") "GENERIC")
        (field (name "AUTHOR") "CERN DEM JLC")
      )
      (libsource (lib "Capacitors") (part "Capacitor - non polarized"))
    )
    (comp (ref "C239")
      (value "220nF")
      (footprint "CAPC0603X33N")
      (description "Non-polarised capacitor")
      (fields
        (field (name "MANUFACTURER PART NUMBER") "CC0201_220NF_6.3V_20%_X5R")
        (field (name "MANUFACTURER") "GENERIC")
        (field (name "AUTHOR") "CERN DEM JLC")
      )
      (libsource (lib "Capacitors") (part "Capacitor - non polarized"))
    )
    (comp (ref "C240")
      (value "470nF")
      (footprint "CAPC0603X33N")
      (description "Non-polarised capacitor")
      (fields
        (field (name "MANUFACTURER PART NUMBER") "CC0201_470NF_4V_20%_X5R")
        (field (name "MANUFACTURER") "GENERIC")
        (field (name "AUTHOR") "CERN DEM JLC")
      )
      (libsource (lib "Capacitors") (part "Capacitor - non polarized"))
    )
    (comp (ref "C241")
      (value "4.7uF")
      (footprint "CAPC1005X55N")
      (description "Non-polarised capacitor")
      (fields
        (field (name "MANUFACTURER PART NUMBER") "CC0402_4.7UF_6.3V_20%_X5R")
        (field (name "MANUFACTURER") "GENERIC")
        (field (name "AUTHOR") "CERN DEM JLC")
      )
      (libsource (lib "Capacitors") (part "Capacitor - non polarized"))
    )
    (comp (ref "C242")
      (value "220nF")
      (footprint "CAPC0603X33N")
      (description "Non-polarised capacitor")
      (fields
        (field (name "MANUFACTURER PART NUMBER") "CC0201_220NF_6.3V_20%_X5R")
        (field (name "MANUFACTURER") "GENERIC")
        (field (name "AUTHOR") "CERN DEM JLC")
      )
      (libsource (lib "Capacitors") (part "Capacitor - non polarized"))
    )
    (comp (ref "C243")
      (value "4.7uF")
      (footprint "CAPC1005X55N")
      (description "Non-polarised capacitor")
      (fields
        (field (name "MANUFACTURER PART NUMBER") "CC0402_4.7UF_6.3V_20%_X5R")
        (field (name "MANUFACTURER") "GENERIC")
        (field (name "AUTHOR") "CERN DEM JLC")
      )
      (libsource (lib "Capacitors") (part "Capacitor - non polarized"))
    )
    (comp (ref "C244")
      (value "100uF")
      (footprint "CAPC3216X180N")
      (description "Non-polarised capacitor")
      (fields
        (field (name "MANUFACTURER PART NUMBER") "CC1206_100UF_6.3V_20%_X5R")
        (field (name "MANUFACTURER") "GENERIC")
        (field (name "AUTHOR") "CERN DEM JLC")
      )
      (libsource (lib "Capacitors") (part "Capacitor - non polarized"))
    )
    (comp (ref "C245")
      (value "100uF")
      (footprint "CAPC3216X180N")
      (description "Non-polarised capacitor")
      (fields
        (field (name "MANUFACTURER PART NUMBER") "CC1206_100UF_6.3V_20%_X5R")
        (field (name "MANUFACTURER") "GENERIC")
        (field (name "AUTHOR") "CERN DEM JLC")
      )
      (libsource (lib "Capacitors") (part "Capacitor - non polarized"))
    )
    (comp (ref "C246")
      (value "100uF")
      (footprint "CAPC3216X180N")
      (description "Non-polarised capacitor")
      (fields
        (field (name "MANUFACTURER PART NUMBER") "CC1206_100UF_6.3V_20%_X5R")
        (field (name "MANUFACTURER") "GENERIC")
        (field (name "AUTHOR") "CERN DEM JLC")
      )
      (libsource (lib "Capacitors") (part "Capacitor - non polarized"))
    )
    (comp (ref "C247")
      (value "100uF")
      (footprint "CAPC3216X180N")
      (description "Non-polarised capacitor")
      (fields
        (field (name "MANUFACTURER PART NUMBER") "CC1206_100UF_6.3V_20%_X5R")
        (field (name "MANUFACTURER") "GENERIC")
        (field (name "AUTHOR") "CERN DEM JLC")
      )
      (libsource (lib "Capacitors") (part "Capacitor - non polarized"))
    )
    (comp (ref "C248")
      (value "100uF")
      (footprint "CAPC3216X180N")
      (description "Non-polarised capacitor")
      (fields
        (field (name "MANUFACTURER PART NUMBER") "CC1206_100UF_6.3V_20%_X5R")
        (field (name "MANUFACTURER") "GENERIC")
        (field (name "AUTHOR") "CERN DEM JLC")
      )
      (libsource (lib "Capacitors") (part "Capacitor - non polarized"))
    )
    (comp (ref "C249")
      (value "100uF")
      (footprint "CAPC3216X180N")
      (description "Non-polarised capacitor")
      (fields
        (field (name "MANUFACTURER PART NUMBER") "CC1206_100UF_6.3V_20%_X5R")
        (field (name "MANUFACTURER") "GENERIC")
        (field (name "AUTHOR") "CERN DEM JLC")
      )
      (libsource (lib "Capacitors") (part "Capacitor - non polarized"))
    )
    (comp (ref "C250")
      (value "100uF")
      (footprint "CAPC3216X180N")
      (description "Non-polarised capacitor")
      (fields
        (field (name "MANUFACTURER PART NUMBER") "CC1206_100UF_6.3V_20%_X5R")
        (field (name "MANUFACTURER") "GENERIC")
        (field (name "AUTHOR") "CERN DEM JLC")
      )
      (libsource (lib "Capacitors") (part "Capacitor - non polarized"))
    )
    (comp (ref "C251")
      (value "100uF")
      (footprint "CAPC3216X180N")
      (description "Non-polarised capacitor")
      (fields
        (field (name "MANUFACTURER PART NUMBER") "CC1206_100UF_6.3V_20%_X5R")
        (field (name "MANUFACTURER") "GENERIC")
        (field (name "AUTHOR") "CERN DEM JLC")
      )
      (libsource (lib "Capacitors") (part "Capacitor - non polarized"))
    )
    (comp (ref "C252")
      (value "100uF")
      (footprint "CAPC3216X180N")
      (description "Non-polarised capacitor")
      (fields
        (field (name "MANUFACTURER PART NUMBER") "CC1206_100UF_6.3V_20%_X5R")
        (field (name "MANUFACTURER") "GENERIC")
        (field (name "AUTHOR") "CERN DEM JLC")
      )
      (libsource (lib "Capacitors") (part "Capacitor - non polarized"))
    )
    (comp (ref "C253")
      (value "4.7uF")
      (footprint "CAPC1005X55N")
      (description "Non-polarised capacitor")
      (fields
        (field (name "MANUFACTURER PART NUMBER") "CC0402_4.7UF_6.3V_20%_X5R")
        (field (name "MANUFACTURER") "GENERIC")
        (field (name "AUTHOR") "CERN DEM JLC")
      )
      (libsource (lib "Capacitors") (part "Capacitor - non polarized"))
    )
    (comp (ref "C254")
      (value "220nF")
      (footprint "CAPC0603X33N")
      (description "Non-polarised capacitor")
      (fields
        (field (name "MANUFACTURER PART NUMBER") "CC0201_220NF_6.3V_20%_X5R")
        (field (name "MANUFACTURER") "GENERIC")
        (field (name "AUTHOR") "CERN DEM JLC")
      )
      (libsource (lib "Capacitors") (part "Capacitor - non polarized"))
    )
    (comp (ref "C255")
      (value "470nF")
      (footprint "CAPC0603X33N")
      (description "Non-polarised capacitor")
      (fields
        (field (name "MANUFACTURER PART NUMBER") "CC0201_470NF_4V_20%_X5R")
        (field (name "MANUFACTURER") "GENERIC")
        (field (name "AUTHOR") "CERN DEM JLC")
      )
      (libsource (lib "Capacitors") (part "Capacitor - non polarized"))
    )
    (comp (ref "C256")
      (value "4.7uF")
      (footprint "CAPC1005X55N")
      (description "Non-polarised capacitor")
      (fields
        (field (name "MANUFACTURER PART NUMBER") "CC0402_4.7UF_6.3V_20%_X5R")
        (field (name "MANUFACTURER") "GENERIC")
        (field (name "AUTHOR") "CERN DEM JLC")
      )
      (libsource (lib "Capacitors") (part "Capacitor - non polarized"))
    )
    (comp (ref "C257")
      (value "220nF")
      (footprint "CAPC0603X33N")
      (description "Non-polarised capacitor")
      (fields
        (field (name "MANUFACTURER PART NUMBER") "CC0201_220NF_6.3V_20%_X5R")
        (field (name "MANUFACTURER") "GENERIC")
        (field (name "AUTHOR") "CERN DEM JLC")
      )
      (libsource (lib "Capacitors") (part "Capacitor - non polarized"))
    )
    (comp (ref "C258")
      (value "4.7uF")
      (footprint "CAPC1005X55N")
      (description "Non-polarised capacitor")
      (fields
        (field (name "MANUFACTURER PART NUMBER") "CC0402_4.7UF_6.3V_20%_X5R")
        (field (name "MANUFACTURER") "GENERIC")
        (field (name "AUTHOR") "CERN DEM JLC")
      )
      (libsource (lib "Capacitors") (part "Capacitor - non polarized"))
    )
    (comp (ref "C259")
      (value "100uF")
      (footprint "CAPC3216X180N")
      (description "Non-polarised capacitor")
      (fields
        (field (name "MANUFACTURER PART NUMBER") "CC1206_100UF_6.3V_20%_X5R")
        (field (name "MANUFACTURER") "GENERIC")
        (field (name "AUTHOR") "CERN DEM JLC")
      )
      (libsource (lib "Capacitors") (part "Capacitor - non polarized"))
    )
    (comp (ref "C260")
      (value "100uF")
      (footprint "CAPC3216X180N")
      (description "Non-polarised capacitor")
      (fields
        (field (name "MANUFACTURER PART NUMBER") "CC1206_100UF_6.3V_20%_X5R")
        (field (name "MANUFACTURER") "GENERIC")
        (field (name "AUTHOR") "CERN DEM JLC")
      )
      (libsource (lib "Capacitors") (part "Capacitor - non polarized"))
    )
    (comp (ref "C261")
      (value "100uF")
      (footprint "CAPC3216X180N")
      (description "Non-polarised capacitor")
      (fields
        (field (name "MANUFACTURER PART NUMBER") "CC1206_100UF_6.3V_20%_X5R")
        (field (name "MANUFACTURER") "GENERIC")
        (field (name "AUTHOR") "CERN DEM JLC")
      )
      (libsource (lib "Capacitors") (part "Capacitor - non polarized"))
    )
    (comp (ref "C262")
      (value "100uF")
      (footprint "CAPC3216X180N")
      (description "Non-polarised capacitor")
      (fields
        (field (name "MANUFACTURER PART NUMBER") "CC1206_100UF_6.3V_20%_X5R")
        (field (name "MANUFACTURER") "GENERIC")
        (field (name "AUTHOR") "CERN DEM JLC")
      )
      (libsource (lib "Capacitors") (part "Capacitor - non polarized"))
    )
    (comp (ref "C263")
      (value "100uF")
      (footprint "CAPC3216X180N")
      (description "Non-polarised capacitor")
      (fields
        (field (name "MANUFACTURER PART NUMBER") "CC1206_100UF_6.3V_20%_X5R")
        (field (name "MANUFACTURER") "GENERIC")
        (field (name "AUTHOR") "CERN DEM JLC")
      )
      (libsource (lib "Capacitors") (part "Capacitor - non polarized"))
    )
    (comp (ref "C264")
      (value "4.7uF")
      (footprint "CAPC1005X55N")
      (description "Non-polarised capacitor")
      (fields
        (field (name "MANUFACTURER PART NUMBER") "CC0402_4.7UF_6.3V_20%_X5R")
        (field (name "MANUFACTURER") "GENERIC")
        (field (name "AUTHOR") "CERN DEM JLC")
      )
      (libsource (lib "Capacitors") (part "Capacitor - non polarized"))
    )
    (comp (ref "C265")
      (value "220nF")
      (footprint "CAPC0603X33N")
      (description "Non-polarised capacitor")
      (fields
        (field (name "MANUFACTURER PART NUMBER") "CC0201_220NF_6.3V_20%_X5R")
        (field (name "MANUFACTURER") "GENERIC")
        (field (name "AUTHOR") "CERN DEM JLC")
      )
      (libsource (lib "Capacitors") (part "Capacitor - non polarized"))
    )
    (comp (ref "C266")
      (value "470nF")
      (footprint "CAPC0603X33N")
      (description "Non-polarised capacitor")
      (fields
        (field (name "MANUFACTURER PART NUMBER") "CC0201_470NF_4V_20%_X5R")
        (field (name "MANUFACTURER") "GENERIC")
        (field (name "AUTHOR") "CERN DEM JLC")
      )
      (libsource (lib "Capacitors") (part "Capacitor - non polarized"))
    )
    (comp (ref "C267")
      (value "4.7uF")
      (footprint "CAPC1005X55N")
      (description "Non-polarised capacitor")
      (fields
        (field (name "MANUFACTURER PART NUMBER") "CC0402_4.7UF_6.3V_20%_X5R")
        (field (name "MANUFACTURER") "GENERIC")
        (field (name "AUTHOR") "CERN DEM JLC")
      )
      (libsource (lib "Capacitors") (part "Capacitor - non polarized"))
    )
    (comp (ref "C268")
      (value "220nF")
      (footprint "CAPC0603X33N")
      (description "Non-polarised capacitor")
      (fields
        (field (name "MANUFACTURER PART NUMBER") "CC0201_220NF_6.3V_20%_X5R")
        (field (name "MANUFACTURER") "GENERIC")
        (field (name "AUTHOR") "CERN DEM JLC")
      )
      (libsource (lib "Capacitors") (part "Capacitor - non polarized"))
    )
    (comp (ref "C269")
      (value "4.7uF")
      (footprint "CAPC1005X55N")
      (description "Non-polarised capacitor")
      (fields
        (field (name "MANUFACTURER PART NUMBER") "CC0402_4.7UF_6.3V_20%_X5R")
        (field (name "MANUFACTURER") "GENERIC")
        (field (name "AUTHOR") "CERN DEM JLC")
      )
      (libsource (lib "Capacitors") (part "Capacitor - non polarized"))
    )
    (comp (ref "C270")
      (value "47uF")
      (footprint "CAPC3225X270N")
      (description "Non-polarised capacitor")
      (fields
        (field (name "MANUFACTURER PART NUMBER") "CC1210_47UF_6.3V_10%_X5R")
        (field (name "MANUFACTURER") "GENERIC")
        (field (name "AUTHOR") "CERN DEM JLC")
      )
      (libsource (lib "Capacitors") (part "Capacitor - non polarized"))
    )
    (comp (ref "C271")
      (value "4.7uF")
      (footprint "CAPC1005X55N")
      (description "Non-polarised capacitor")
      (fields
        (field (name "MANUFACTURER PART NUMBER") "CC0402_4.7UF_6.3V_20%_X5R")
        (field (name "MANUFACTURER") "GENERIC")
        (field (name "AUTHOR") "CERN DEM JLC")
      )
      (libsource (lib "Capacitors") (part "Capacitor - non polarized"))
    )
    (comp (ref "C272")
      (value "4.7uF")
      (footprint "CAPC1005X55N")
      (description "Non-polarised capacitor")
      (fields
        (field (name "MANUFACTURER PART NUMBER") "CC0402_4.7UF_6.3V_20%_X5R")
        (field (name "MANUFACTURER") "GENERIC")
        (field (name "AUTHOR") "CERN DEM JLC")
      )
      (libsource (lib "Capacitors") (part "Capacitor - non polarized"))
    )
    (comp (ref "C273")
      (value "4.7uF")
      (footprint "CAPC1005X55N")
      (description "Non-polarised capacitor")
      (fields
        (field (name "MANUFACTURER PART NUMBER") "CC0402_4.7UF_6.3V_20%_X5R")
        (field (name "MANUFACTURER") "GENERIC")
        (field (name "AUTHOR") "CERN DEM JLC")
      )
      (libsource (lib "Capacitors") (part "Capacitor - non polarized"))
    )
    (comp (ref "C274")
      (value "4.7uF")
      (footprint "CAPC1005X55N")
      (description "Non-polarised capacitor")
      (fields
        (field (name "MANUFACTURER PART NUMBER") "CC0402_4.7UF_6.3V_20%_X5R")
        (field (name "MANUFACTURER") "GENERIC")
        (field (name "AUTHOR") "CERN DEM JLC")
      )
      (libsource (lib "Capacitors") (part "Capacitor - non polarized"))
    )
    (comp (ref "C275")
      (value "4.7uF")
      (footprint "CAPC1005X55N")
      (description "Non-polarised capacitor")
      (fields
        (field (name "MANUFACTURER PART NUMBER") "CC0402_4.7UF_6.3V_20%_X5R")
        (field (name "MANUFACTURER") "GENERIC")
        (field (name "AUTHOR") "CERN DEM JLC")
      )
      (libsource (lib "Capacitors") (part "Capacitor - non polarized"))
    )
    (comp (ref "C276")
      (value "4.7uF")
      (footprint "CAPC1005X55N")
      (description "Non-polarised capacitor")
      (fields
        (field (name "MANUFACTURER PART NUMBER") "CC0402_4.7UF_6.3V_20%_X5R")
        (field (name "MANUFACTURER") "GENERIC")
        (field (name "AUTHOR") "CERN DEM JLC")
      )
      (libsource (lib "Capacitors") (part "Capacitor - non polarized"))
    )
    (comp (ref "C277")
      (value "100uF")
      (footprint "CAPC3216X180N")
      (description "Non-polarised capacitor")
      (fields
        (field (name "MANUFACTURER PART NUMBER") "CC1206_100UF_6.3V_20%_X5R")
        (field (name "MANUFACTURER") "GENERIC")
        (field (name "AUTHOR") "CERN DEM JLC")
      )
      (libsource (lib "Capacitors") (part "Capacitor - non polarized"))
    )
    (comp (ref "C278")
      (value "4.7uF")
      (footprint "CAPC1005X55N")
      (description "Non-polarised capacitor")
      (fields
        (field (name "MANUFACTURER PART NUMBER") "CC0402_4.7UF_6.3V_20%_X5R")
        (field (name "MANUFACTURER") "GENERIC")
        (field (name "AUTHOR") "CERN DEM JLC")
      )
      (libsource (lib "Capacitors") (part "Capacitor - non polarized"))
    )
    (comp (ref "C279")
      (value "4.7uF")
      (footprint "CAPC1005X55N")
      (description "Non-polarised capacitor")
      (fields
        (field (name "MANUFACTURER PART NUMBER") "CC0402_4.7UF_6.3V_20%_X5R")
        (field (name "MANUFACTURER") "GENERIC")
        (field (name "AUTHOR") "CERN DEM JLC")
      )
      (libsource (lib "Capacitors") (part "Capacitor - non polarized"))
    )
    (comp (ref "C280")
      (value "4.7uF")
      (footprint "CAPC1005X55N")
      (description "Non-polarised capacitor")
      (fields
        (field (name "MANUFACTURER PART NUMBER") "CC0402_4.7UF_6.3V_20%_X5R")
        (field (name "MANUFACTURER") "GENERIC")
        (field (name "AUTHOR") "CERN DEM JLC")
      )
      (libsource (lib "Capacitors") (part "Capacitor - non polarized"))
    )
    (comp (ref "C281")
      (value "4.7uF")
      (footprint "CAPC1005X55N")
      (description "Non-polarised capacitor")
      (fields
        (field (name "MANUFACTURER PART NUMBER") "CC0402_4.7UF_6.3V_20%_X5R")
        (field (name "MANUFACTURER") "GENERIC")
        (field (name "AUTHOR") "CERN DEM JLC")
      )
      (libsource (lib "Capacitors") (part "Capacitor - non polarized"))
    )
    (comp (ref "C282")
      (value "4.7uF")
      (footprint "CAPC1005X55N")
      (description "Non-polarised capacitor")
      (fields
        (field (name "MANUFACTURER PART NUMBER") "CC0402_4.7UF_6.3V_20%_X5R")
        (field (name "MANUFACTURER") "GENERIC")
        (field (name "AUTHOR") "CERN DEM JLC")
      )
      (libsource (lib "Capacitors") (part "Capacitor - non polarized"))
    )
    (comp (ref "C283")
      (value "4.7uF")
      (footprint "CAPC1005X55N")
      (description "Non-polarised capacitor")
      (fields
        (field (name "MANUFACTURER PART NUMBER") "CC0402_4.7UF_6.3V_20%_X5R")
        (field (name "MANUFACTURER") "GENERIC")
        (field (name "AUTHOR") "CERN DEM JLC")
      )
      (libsource (lib "Capacitors") (part "Capacitor - non polarized"))
    )
  )
  (nets
    (net (code "1") (name "GND") (class "Default")
      (node (ref "C160") (pin "1") (pinfunction "1_1") (pintype "passive"))
      (node (ref "C161") (pin "1") (pinfunction "1_1") (pintype "passive"))
      (node (ref "C162") (pin "1") (pinfunction "1_1") (pintype "passive"))
      (node (ref "C163") (pin "1") (pinfunction "1_1") (pintype "passive"))
      (node (ref "C164") (pin "1") (pinfunction "1_1") (pintype "passive"))
      (node (ref "C165") (pin "1") (pinfunction "1_1") (pintype "passive"))
      (node (ref "C166") (pin "1") (pinfunction "1_1") (pintype "passive"))
      (node (ref "C167") (pin "1") (pinfunction "1_1") (pintype "passive"))
      (node (ref "C168") (pin "1") (pinfunction "1_1") (pintype "passive"))
      (node (ref "C169") (pin "1") (pinfunction "1_1") (pintype "passive"))
      (node (ref "C170") (pin "1") (pinfunction "1_1") (pintype "passive"))
      (node (ref "C171") (pin "1") (pinfunction "1_1") (pintype "passive"))
      (node (ref "C172") (pin "1") (pinfunction "1_1") (pintype "passive"))
      (node (ref "C173") (pin "1") (pinfunction "1_1") (pintype "passive"))
      (node (ref "C174") (pin "1") (pinfunction "1_1") (pintype "passive"))
      (node (ref "C175") (pin "1") (pinfunction "1_1") (pintype "passive"))
      (node (ref "C176") (pin "1") (pinfunction "1_1") (pintype "passive"))
      (node (ref "C177") (pin "1") (pinfunction "1_1") (pintype "passive"))
      (node (ref "C178") (pin "1") (pinfunction "1_1") (pintype "passive"))
      (node (ref "C179") (pin "1") (pinfunction "1_1") (pintype "passive"))
      (node (ref "C180") (pin "2") (pinfunction "2_2") (pintype "passive"))
      (node (ref "C181") (pin "2") (pinfunction "2_2") (pintype "passive"))
      (node (ref "C182") (pin "2") (pinfunction "2_2") (pintype "passive"))
      (node (ref "C183") (pin "2") (pinfunction "2_2") (pintype "passive"))
      (node (ref "C184") (pin "2") (pinfunction "2_2") (pintype "passive"))
      (node (ref "C185") (pin "2") (pinfunction "2_2") (pintype "passive"))
      (node (ref "C186") (pin "2") (pinfunction "2_2") (pintype "passive"))
      (node (ref "C187") (pin "2") (pinfunction "2_2") (pintype "passive"))
      (node (ref "C188") (pin "1") (pinfunction "1_1") (pintype "passive"))
      (node (ref "C189") (pin "1") (pinfunction "1_1") (pintype "passive"))
      (node (ref "C190") (pin "1") (pinfunction "1_1") (pintype "passive"))
      (node (ref "C191") (pin "1") (pinfunction "1_1") (pintype "passive"))
      (node (ref "C192") (pin "1") (pinfunction "1_1") (pintype "passive"))
      (node (ref "C193") (pin "1") (pinfunction "1_1") (pintype "passive"))
      (node (ref "C194") (pin "1") (pinfunction "1_1") (pintype "passive"))
      (node (ref "C195") (pin "1") (pinfunction "1_1") (pintype "passive"))
      (node (ref "C196") (pin "1") (pinfunction "1_1") (pintype "passive"))
      (node (ref "C197") (pin "1") (pinfunction "1_1") (pintype "passive"))
      (node (ref "C198") (pin "1") (pinfunction "1_1") (pintype "passive"))
      (node (ref "C199") (pin "1") (pinfunction "1_1") (pintype "passive"))
      (node (ref "C200") (pin "1") (pinfunction "1_1") (pintype "passive"))
      (node (ref "C201") (pin "1") (pinfunction "1_1") (pintype "passive"))
      (node (ref "C202") (pin "1") (pinfunction "1_1") (pintype "passive"))
      (node (ref "C203") (pin "1") (pinfunction "1_1") (pintype "passive"))
      (node (ref "C204") (pin "1") (pinfunction "1_1") (pintype "passive"))
      (node (ref "C205") (pin "1") (pinfunction "1_1") (pintype "passive"))
      (node (ref "C206") (pin "1") (pinfunction "1_1") (pintype "passive"))
      (node (ref "C207") (pin "1") (pinfunction "1_1") (pintype "passive"))
      (node (ref "C208") (pin "1") (pinfunction "1_1") (pintype "passive"))
      (node (ref "C209") (pin "1") (pinfunction "1_1") (pintype "passive"))
      (node (ref "C210") (pin "1") (pinfunction "1_1") (pintype "passive"))
      (node (ref "C211") (pin "1") (pinfunction "1_1") (pintype "passive"))
      (node (ref "C212") (pin "1") (pinfunction "1_1") (pintype "passive"))
      (node (ref "C213") (pin "1") (pinfunction "1_1") (pintype "passive"))
      (node (ref "C214") (pin "1") (pinfunction "1_1") (pintype "passive"))
      (node (ref "C215") (pin "1") (pinfunction "1_1") (pintype "passive"))
      (node (ref "C216") (pin "1") (pinfunction "1_1") (pintype "passive"))
      (node (ref "C217") (pin "1") (pinfunction "1_1") (pintype "passive"))
      (node (ref "C218") (pin "1") (pinfunction "1_1") (pintype "passive"))
      (node (ref "C219") (pin "1") (pinfunction "1_1") (pintype "passive"))
      (node (ref "C220") (pin "1") (pinfunction "1_1") (pintype "passive"))
      (node (ref "C221") (pin "1") (pinfunction "1_1") (pintype "passive"))
      (node (ref "C222") (pin "1") (pinfunction "1_1") (pintype "passive"))
      (node (ref "C223") (pin "1") (pinfunction "1_1") (pintype "passive"))
      (node (ref "C224") (pin "1") (pinfunction "1_1") (pintype "passive"))
      (node (ref "C225") (pin "1") (pinfunction "1_1") (pintype "passive"))
      (node (ref "C226") (pin "1") (pinfunction "1_1") (pintype "passive"))
      (node (ref "C227") (pin "1") (pinfunction "1_1") (pintype "passive"))
      (node (ref "C228") (pin "1") (pinfunction "1_1") (pintype "passive"))
      (node (ref "C229") (pin "1") (pinfunction "1_1") (pintype "passive"))
      (node (ref "C230") (pin "1") (pinfunction "1_1") (pintype "passive"))
      (node (ref "C231") (pin "1") (pinfunction "1_1") (pintype "passive"))
      (node (ref "C232") (pin "1") (pinfunction "1_1") (pintype "passive"))
      (node (ref "C233") (pin "1") (pinfunction "1_1") (pintype "passive"))
      (node (ref "C234") (pin "1") (pinfunction "1_1") (pintype "passive"))
      (node (ref "C235") (pin "1") (pinfunction "1_1") (pintype "passive"))
      (node (ref "C236") (pin "1") (pinfunction "1_1") (pintype "passive"))
      (node (ref "C237") (pin "1") (pinfunction "1_1") (pintype "passive"))
      (node (ref "C238") (pin "1") (pinfunction "1_1") (pintype "passive"))
      (node (ref "C239") (pin "1") (pinfunction "1_1") (pintype "passive"))
      (node (ref "C240") (pin "1") (pinfunction "1_1") (pintype "passive"))
      (node (ref "C241") (pin "1") (pinfunction "1_1") (pintype "passive"))
      (node (ref "C242") (pin "1") (pinfunction "1_1") (pintype "passive"))
      (node (ref "C243") (pin "1") (pinfunction "1_1") (pintype "passive"))
      (node (ref "C244") (pin "1") (pinfunction "1_1") (pintype "passive"))
      (node (ref "C245") (pin "1") (pinfunction "1_1") (pintype "passive"))
      (node (ref "C246") (pin "1") (pinfunction "1_1") (pintype "passive"))
      (node (ref "C247") (pin "1") (pinfunction "1_1") (pintype "passive"))
      (node (ref "C248") (pin "1") (pinfunction "1_1") (pintype "passive"))
      (node (ref "C249") (pin "1") (pinfunction "1_1") (pintype "passive"))
      (node (ref "C250") (pin "1") (pinfunction "1_1") (pintype "passive"))
      (node (ref "C251") (pin "1") (pinfunction "1_1") (pintype "passive"))
      (node (ref "C252") (pin "1") (pinfunction "1_1") (pintype "passive"))
      (node (ref "C253") (pin "1") (pinfunction "1_1") (pintype "passive"))
      (node (ref "C254") (pin "1") (pinfunction "1_1") (pintype "passive"))
      (node (ref "C255") (pin "1") (pinfunction "1_1") (pintype "passive"))
      (node (ref "C256") (pin "1") (pinfunction "1_1") (pintype "passive"))
      (node (ref "C257") (pin "1") (pinfunction "1_1") (pintype "passive"))
      (node (ref "C258") (pin "1") (pinfunction "1_1") (pintype "passive"))
      (node (ref "C259") (pin "1") (pinfunction "1_1") (pintype "passive"))
      (node (ref "C260") (pin "1") (pinfunction "1_1") (pintype "passive"))
      (node (ref "C261") (pin "1") (pinfunction "1_1") (pintype "passive"))
      (node (ref "C262") (pin "1") (pinfunction "1_1") (pintype "passive"))
      (node (ref "C263") (pin "1") (pinfunction "1_1") (pintype "passive"))
      (node (ref "C264") (pin "1") (pinfunction "1_1") (pintype "passive"))
      (node (ref "C265") (pin "1") (pinfunction "1_1") (pintype "passive"))
      (node (ref "C266") (pin "1") (pinfunction "1_1") (pintype "passive"))
      (node (ref "C267") (pin "1") (pinfunction "1_1") (pintype "passive"))
      (node (ref "C268") (pin "1") (pinfunction "1_1") (pintype "passive"))
      (node (ref "C269") (pin "1") (pinfunction "1_1") (pintype "passive"))
      (node (ref "C270") (pin "1") (pinfunction "1_1") (pintype "passive"))
      (node (ref "C271") (pin "1") (pinfunction "1_1") (pintype "passive"))
      (node (ref "C272") (pin "1") (pinfunction "1_1") (pintype "passive"))
      (node (ref "C273") (pin "1") (pinfunction "1_1") (pintype "passive"))
      (node (ref "C274") (pin "1") (pinfunction "1_1") (pintype "passive"))
      (node (ref "C275") (pin "1") (pinfunction "1_1") (pintype "passive"))
      (node (ref "C276") (pin "1") (pinfunction "1_1") (pintype "passive"))
      (node (ref "C277") (pin "1") (pinfunction "1_1") (pintype "passive"))
      (node (ref "C278") (pin "1") (pinfunction "1_1") (pintype "passive"))
      (node (ref "C279") (pin "1") (pinfunction "1_1") (pintype "passive"))
      (node (ref "C280") (pin "1") (pinfunction "1_1") (pintype "passive"))
      (node (ref "C281") (pin "1") (pinfunction "1_1") (pintype "passive"))
      (node (ref "C282") (pin "1") (pinfunction "1_1") (pintype "passive"))
      (node (ref "C283") (pin "1") (pinfunction "1_1") (pintype "passive"))
    )
    (net (code "2") (name "MGTAVCC") (class "Default")
      (node (ref "C160") (pin "2") (pinfunction "2_2") (pintype "passive"))
      (node (ref "C161") (pin "2") (pinfunction "2_2") (pintype "passive"))
      (node (ref "C198") (pin "2") (pinfunction "2_2") (pintype "passive"))
      (node (ref "C199") (pin "2") (pinfunction "2_2") (pintype "passive"))
      (node (ref "C200") (pin "2") (pinfunction "2_2") (pintype "passive"))
      (node (ref "C201") (pin "2") (pinfunction "2_2") (pintype "passive"))
      (node (ref "C202") (pin "2") (pinfunction "2_2") (pintype "passive"))
      (node (ref "C203") (pin "2") (pinfunction "2_2") (pintype "passive"))
      (node (ref "C204") (pin "2") (pinfunction "2_2") (pintype "passive"))
      (node (ref "C205") (pin "2") (pinfunction "2_2") (pintype "passive"))
      (node (ref "C219") (pin "2") (pinfunction "2_2") (pintype "passive"))
      (node (ref "C220") (pin "2") (pinfunction "2_2") (pintype "passive"))
      (node (ref "C221") (pin "2") (pinfunction "2_2") (pintype "passive"))
      (node (ref "C222") (pin "2") (pinfunction "2_2") (pintype "passive"))
      (node (ref "C223") (pin "2") (pinfunction "2_2") (pintype "passive"))
      (node (ref "C224") (pin "2") (pinfunction "2_2") (pintype "passive"))
      (node (ref "C225") (pin "2") (pinfunction "2_2") (pintype "passive"))
      (node (ref "C226") (pin "2") (pinfunction "2_2") (pintype "passive"))
      (node (ref "C238") (pin "2") (pinfunction "2_2") (pintype "passive"))
      (node (ref "C239") (pin "2") (pinfunction "2_2") (pintype "passive"))
      (node (ref "C240") (pin "2") (pinfunction "2_2") (pintype "passive"))
      (node (ref "C253") (pin "2") (pinfunction "2_2") (pintype "passive"))
      (node (ref "C254") (pin "2") (pinfunction "2_2") (pintype "passive"))
      (node (ref "C255") (pin "2") (pinfunction "2_2") (pintype "passive"))
      (node (ref "C264") (pin "2") (pinfunction "2_2") (pintype "passive"))
      (node (ref "C265") (pin "2") (pinfunction "2_2") (pintype "passive"))
      (node (ref "C266") (pin "2") (pinfunction "2_2") (pintype "passive"))
    )
    (net (code "3") (name "MGTAVTT") (class "Default")
      (node (ref "C206") (pin "2") (pinfunction "2_2") (pintype "passive"))
      (node (ref "C207") (pin "2") (pinfunction "2_2") (pintype "passive"))
      (node (ref "C227") (pin "2") (pinfunction "2_2") (pintype "passive"))
      (node (ref "C228") (pin "2") (pinfunction "2_2") (pintype "passive"))
      (node (ref "C236") (pin "2") (pinfunction "2_2") (pintype "passive"))
      (node (ref "C237") (pin "2") (pinfunction "2_2") (pintype "passive"))
      (node (ref "C241") (pin "2") (pinfunction "2_2") (pintype "passive"))
      (node (ref "C242") (pin "2") (pinfunction "2_2") (pintype "passive"))
      (node (ref "C244") (pin "2") (pinfunction "2_2") (pintype "passive"))
      (node (ref "C245") (pin "2") (pinfunction "2_2") (pintype "passive"))
      (node (ref "C246") (pin "2") (pinfunction "2_2") (pintype "passive"))
      (node (ref "C247") (pin "2") (pinfunction "2_2") (pintype "passive"))
      (node (ref "C248") (pin "2") (pinfunction "2_2") (pintype "passive"))
      (node (ref "C256") (pin "2") (pinfunction "2_2") (pintype "passive"))
      (node (ref "C257") (pin "2") (pinfunction "2_2") (pintype "passive"))
      (node (ref "C259") (pin "2") (pinfunction "2_2") (pintype "passive"))
      (node (ref "C260") (pin "2") (pinfunction "2_2") (pintype "passive"))
      (node (ref "C261") (pin "2") (pinfunction "2_2") (pintype "passive"))
      (node (ref "C262") (pin "2") (pinfunction "2_2") (pintype "passive"))
      (node (ref "C263") (pin "2") (pinfunction "2_2") (pintype "passive"))
      (node (ref "C267") (pin "2") (pinfunction "2_2") (pintype "passive"))
      (node (ref "C268") (pin "2") (pinfunction "2_2") (pintype "passive"))
    )
    (net (code "4") (name "MGTVCCAUX") (class "Default")
      (node (ref "C208") (pin "2") (pinfunction "2_2") (pintype "passive"))
      (node (ref "C229") (pin "2") (pinfunction "2_2") (pintype "passive"))
      (node (ref "C243") (pin "2") (pinfunction "2_2") (pintype "passive"))
      (node (ref "C258") (pin "2") (pinfunction "2_2") (pintype "passive"))
      (node (ref "C269") (pin "2") (pinfunction "2_2") (pintype "passive"))
    )
    (net (code "5") (name "P1V5") (class "Default")
      (node (ref "C193") (pin "2") (pinfunction "2_2") (pintype "passive"))
      (node (ref "C194") (pin "2") (pinfunction "2_2") (pintype "passive"))
      (node (ref "C195") (pin "2") (pinfunction "2_2") (pintype "passive"))
      (node (ref "C196") (pin "2") (pinfunction "2_2") (pintype "passive"))
      (node (ref "C197") (pin "2") (pinfunction "2_2") (pintype "passive"))
      (node (ref "C249") (pin "2") (pinfunction "2_2") (pintype "passive"))
      (node (ref "C277") (pin "2") (pinfunction "2_2") (pintype "passive"))
      (node (ref "C278") (pin "2") (pinfunction "2_2") (pintype "passive"))
      (node (ref "C279") (pin "2") (pinfunction "2_2") (pintype "passive"))
      (node (ref "C280") (pin "2") (pinfunction "2_2") (pintype "passive"))
      (node (ref "C281") (pin "2") (pinfunction "2_2") (pintype "passive"))
      (node (ref "C282") (pin "2") (pinfunction "2_2") (pintype "passive"))
      (node (ref "C283") (pin "2") (pinfunction "2_2") (pintype "passive"))
    )
    (net (code "6") (name "P1V8") (class "Default")
      (node (ref "C188") (pin "2") (pinfunction "2_2") (pintype "passive"))
      (node (ref "C189") (pin "2") (pinfunction "2_2") (pintype "passive"))
      (node (ref "C190") (pin "2") (pinfunction "2_2") (pintype "passive"))
      (node (ref "C191") (pin "2") (pinfunction "2_2") (pintype "passive"))
      (node (ref "C192") (pin "2") (pinfunction "2_2") (pintype "passive"))
      (node (ref "C250") (pin "2") (pinfunction "2_2") (pintype "passive"))
      (node (ref "C251") (pin "2") (pinfunction "2_2") (pintype "passive"))
      (node (ref "C252") (pin "2") (pinfunction "2_2") (pintype "passive"))
    )
    (net (code "7") (name "P3V3") (class "Default")
      (node (ref "C270") (pin "2") (pinfunction "2_2") (pintype "passive"))
      (node (ref "C271") (pin "2") (pinfunction "2_2") (pintype "passive"))
      (node (ref "C272") (pin "2") (pinfunction "2_2") (pintype "passive"))
      (node (ref "C273") (pin "2") (pinfunction "2_2") (pintype "passive"))
      (node (ref "C274") (pin "2") (pinfunction "2_2") (pintype "passive"))
      (node (ref "C275") (pin "2") (pinfunction "2_2") (pintype "passive"))
      (node (ref "C276") (pin "2") (pinfunction "2_2") (pintype "passive"))
    )
    (net (code "8") (name "VCCAUX") (class "Default")
      (node (ref "C230") (pin "2") (pinfunction "2_2") (pintype "passive"))
      (node (ref "C231") (pin "2") (pinfunction "2_2") (pintype "passive"))
      (node (ref "C232") (pin "2") (pinfunction "2_2") (pintype "passive"))
      (node (ref "C233") (pin "2") (pinfunction "2_2") (pintype "passive"))
      (node (ref "C234") (pin "2") (pinfunction "2_2") (pintype "passive"))
      (node (ref "C235") (pin "2") (pinfunction "2_2") (pintype "passive"))
    )
    (net (code "9") (name "VCCBRAM") (class "Default")
      (node (ref "C209") (pin "2") (pinfunction "2_2") (pintype "passive"))
      (node (ref "C210") (pin "2") (pinfunction "2_2") (pintype "passive"))
      (node (ref "C211") (pin "2") (pinfunction "2_2") (pintype "passive"))
      (node (ref "C212") (pin "2") (pinfunction "2_2") (pintype "passive"))
      (node (ref "C213") (pin "2") (pinfunction "2_2") (pintype "passive"))
      (node (ref "C214") (pin "2") (pinfunction "2_2") (pintype "passive"))
      (node (ref "C215") (pin "2") (pinfunction "2_2") (pintype "passive"))
      (node (ref "C216") (pin "2") (pinfunction "2_2") (pintype "passive"))
      (node (ref "C217") (pin "2") (pinfunction "2_2") (pintype "passive"))
      (node (ref "C218") (pin "2") (pinfunction "2_2") (pintype "passive"))
    )
    (net (code "10") (name "VCCINT") (class "Default")
      (node (ref "C162") (pin "2") (pinfunction "2_2") (pintype "passive"))
      (node (ref "C163") (pin "2") (pinfunction "2_2") (pintype "passive"))
      (node (ref "C164") (pin "2") (pinfunction "2_2") (pintype "passive"))
      (node (ref "C165") (pin "2") (pinfunction "2_2") (pintype "passive"))
      (node (ref "C166") (pin "2") (pinfunction "2_2") (pintype "passive"))
      (node (ref "C167") (pin "2") (pinfunction "2_2") (pintype "passive"))
      (node (ref "C168") (pin "2") (pinfunction "2_2") (pintype "passive"))
      (node (ref "C169") (pin "2") (pinfunction "2_2") (pintype "passive"))
      (node (ref "C170") (pin "2") (pinfunction "2_2") (pintype "passive"))
      (node (ref "C171") (pin "2") (pinfunction "2_2") (pintype "passive"))
      (node (ref "C172") (pin "2") (pinfunction "2_2") (pintype "passive"))
      (node (ref "C173") (pin "2") (pinfunction "2_2") (pintype "passive"))
      (node (ref "C174") (pin "2") (pinfunction "2_2") (pintype "passive"))
      (node (ref "C175") (pin "2") (pinfunction "2_2") (pintype "passive"))
      (node (ref "C176") (pin "2") (pinfunction "2_2") (pintype "passive"))
      (node (ref "C177") (pin "2") (pinfunction "2_2") (pintype "passive"))
      (node (ref "C178") (pin "2") (pinfunction "2_2") (pintype "passive"))
      (node (ref "C179") (pin "2") (pinfunction "2_2") (pintype "passive"))
      (node (ref "C180") (pin "1") (pinfunction "1_1") (pintype "passive"))
      (node (ref "C181") (pin "1") (pinfunction "1_1") (pintype "passive"))
      (node (ref "C182") (pin "1") (pinfunction "1_1") (pintype "passive"))
      (node (ref "C183") (pin "1") (pinfunction "1_1") (pintype "passive"))
      (node (ref "C184") (pin "1") (pinfunction "1_1") (pintype "passive"))
      (node (ref "C185") (pin "1") (pinfunction "1_1") (pintype "passive"))
      (node (ref "C186") (pin "1") (pinfunction "1_1") (pintype "passive"))
      (node (ref "C187") (pin "1") (pinfunction "1_1") (pintype "passive"))
    )
  )
)
